# 12-multimodal-RTC.net
KiCad netlist of a schematic drawn in Altium Designer
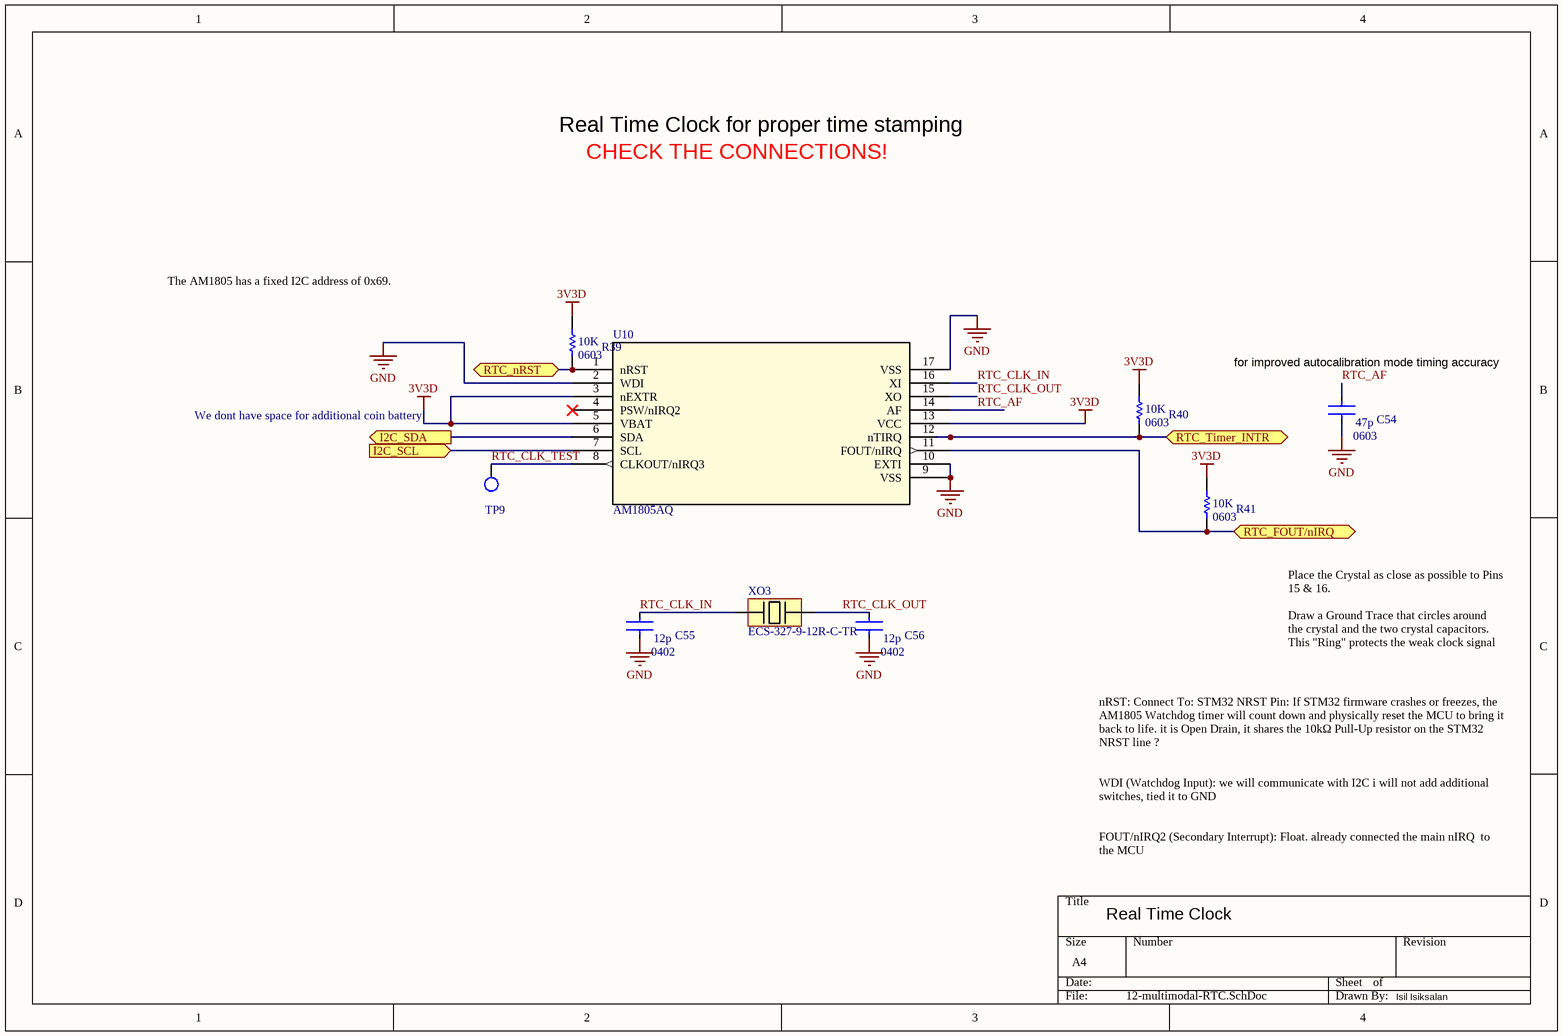
[diagram p0: 12-multimodal-RTC.SchDoc]

(export (version "E")
  (design (tool "Eeschema 10.0.6"))
  (components
    (comp (ref "C54")
      (value "CGA3E2C0G1H470J080AA")
      (footprint "CAPTDK0603")
      (description "CAP CER 47PF 50V C0G 0603")
      (libsource (lib "multimodal") (part "CGA3E2C0G1H470J080AA"))
    )
    (comp (ref "C55")
      (value "CGA2B2C0G1H120J050BA")
      (footprint "CAPTDK0402")
      (description "CAP CER 12PF 50V C0G 0402")
      (libsource (lib "multimodal") (part "CGA2B2C0G1H120J050BA"))
    )
    (comp (ref "C56")
      (value "CGA2B2C0G1H120J050BA")
      (footprint "CAPTDK0402")
      (description "CAP CER 12PF 50V C0G 0402")
      (libsource (lib "multimodal") (part "CGA2B2C0G1H120J050BA"))
    )
    (comp (ref "R39")
      (value "RMCF0603JG10K0")
      (footprint "RES-STACK-POLE-0603")
      (description "RES 10K OHM 5% 1/10W 0603")
      (libsource (lib "multimodal") (part "RMCF0603JG10K0"))
    )
    (comp (ref "R40")
      (value "RMCF0603JG10K0")
      (footprint "RES-STACK-POLE-0603")
      (description "RES 10K OHM 5% 1/10W 0603")
      (libsource (lib "multimodal") (part "RMCF0603JG10K0"))
    )
    (comp (ref "R41")
      (value "RMCF0603JG10K0")
      (footprint "RES-STACK-POLE-0603")
      (description "RES 10K OHM 5% 1/10W 0603")
      (libsource (lib "multimodal") (part "RMCF0603JG10K0"))
    )
    (comp (ref "TP9")
      (value "TESTPOINT_S")
      (footprint "TESTPOINT_S")
      (description "Testpoint Surface Pad")
      (libsource (lib "multimodal") (part "TESTPOINT_S"))
    )
    (comp (ref "U10")
      (value "AM1805AQ")
      (footprint "QFN16_AM1805AQ_ABQ")
      (description "RTC ARTASIE I2C W/PWR MNGT 16QFN")
      (fields
        (field (name "MANUFACTURER_PART_NUMBER") "AM1815AQ")
        (field (name "COPYRIGHT") "Copyright (C) 2026 Ultra Librarian. All rights reserved.")
      )
      (libsource (lib "multimodal") (part "AM1805AQ"))
    )
    (comp (ref "XO3")
      (value "ECS-327-9-12R-C-TR")
      (footprint "LSE-32K")
      (description "Crystal 0.032768MHz ±10ppm (Tol) 9pF Flexural 70000Ohm Automotive 2-Pin Ultra Mini-CSMD T/R")
      (fields
        (field (name "MANUFACTURER") "ECS International")
        (field (name "MANUFACTURER PART NUMBER") "ECS-.327-9-12R-C-TR")
      )
      (libsource (lib "multimodal") (part "ECS-327-9-12R-C-TR"))
    )
  )
  (nets
    (net (code "1") (name "/I2C_SCL") (class "Default")
      (node (ref "U10") (pin "7") (pinfunction "SCL_7") (pintype "passive"))
    )
    (net (code "2") (name "/I2C_SDA") (class "Default")
      (node (ref "U10") (pin "6") (pinfunction "SDA_6") (pintype "passive"))
    )
    (net (code "3") (name "/RTC_AF") (class "Default")
      (node (ref "C54") (pin "1") (pinfunction "1_1") (pintype "passive"))
      (node (ref "U10") (pin "14") (pinfunction "AF_14") (pintype "passive"))
    )
    (net (code "4") (name "/RTC_CLK_IN") (class "Default")
      (node (ref "C55") (pin "1") (pinfunction "1_1") (pintype "passive"))
      (node (ref "U10") (pin "16") (pinfunction "XI_16") (pintype "passive"))
      (node (ref "XO3") (pin "1") (pinfunction "1_1") (pintype "passive"))
    )
    (net (code "5") (name "/RTC_CLK_OUT") (class "Default")
      (node (ref "C56") (pin "1") (pinfunction "1_1") (pintype "passive"))
      (node (ref "U10") (pin "15") (pinfunction "XO_15") (pintype "passive"))
      (node (ref "XO3") (pin "2") (pinfunction "2_2") (pintype "passive"))
    )
    (net (code "6") (name "/RTC_CLK_TEST") (class "Default")
      (node (ref "TP9") (pin "1") (pinfunction "1_1") (pintype "passive"))
      (node (ref "U10") (pin "8") (pinfunction "CLKOUT/nIRQ3_8") (pintype "output"))
    )
    (net (code "7") (name "/RTC_FOUT{slash}nIRQ") (class "Default")
      (node (ref "R41") (pin "1") (pinfunction "1_1") (pintype "passive"))
      (node (ref "U10") (pin "11") (pinfunction "FOUT/nIRQ_11") (pintype "output"))
    )
    (net (code "8") (name "/RTC_Timer_INTR") (class "Default")
      (node (ref "R40") (pin "1") (pinfunction "1_1") (pintype "passive"))
      (node (ref "U10") (pin "12") (pinfunction "nTIRQ_12") (pintype "passive"))
    )
    (net (code "9") (name "/RTC_nRST") (class "Default")
      (node (ref "R39") (pin "1") (pinfunction "1_1") (pintype "passive"))
      (node (ref "U10") (pin "1") (pinfunction "nRST_1") (pintype "passive"))
    )
    (net (code "10") (name "3V3D") (class "Default")
      (node (ref "R39") (pin "2") (pinfunction "2_2") (pintype "passive"))
      (node (ref "R40") (pin "2") (pinfunction "2_2") (pintype "passive"))
      (node (ref "R41") (pin "2") (pinfunction "2_2") (pintype "passive"))
      (node (ref "U10") (pin "13") (pinfunction "VCC_13") (pintype "power_in"))
      (node (ref "U10") (pin "3") (pinfunction "nEXTR_3") (pintype "passive"))
      (node (ref "U10") (pin "5") (pinfunction "VBAT_5") (pintype "passive"))
    )
    (net (code "11") (name "GND") (class "Default")
      (node (ref "C54") (pin "2") (pinfunction "2_2") (pintype "passive"))
      (node (ref "C55") (pin "2") (pinfunction "2_2") (pintype "passive"))
      (node (ref "C56") (pin "2") (pinfunction "2_2") (pintype "passive"))
      (node (ref "U10") (pin "10") (pinfunction "EXTI_10") (pintype "passive"))
      (node (ref "U10") (pin "17") (pinfunction "VSS_17") (pintype "power_in"))
      (node (ref "U10") (pin "2") (pinfunction "WDI_2") (pintype "passive"))
      (node (ref "U10") (pin "9") (pinfunction "VSS_9") (pintype "passive"))
    )
    (net (code "12") (name "unconnected-(U10-PSW{slash}nIRQ2-Pad4)") (class "Default")
      (node (ref "U10") (pin "4") (pinfunction "PSW/nIRQ2_4") (pintype "passive+no_connect"))
    )
  )
)
